# PIC18-USB_ICSP-Board.net
KiCad netlist of a schematic drawn in EAGLE
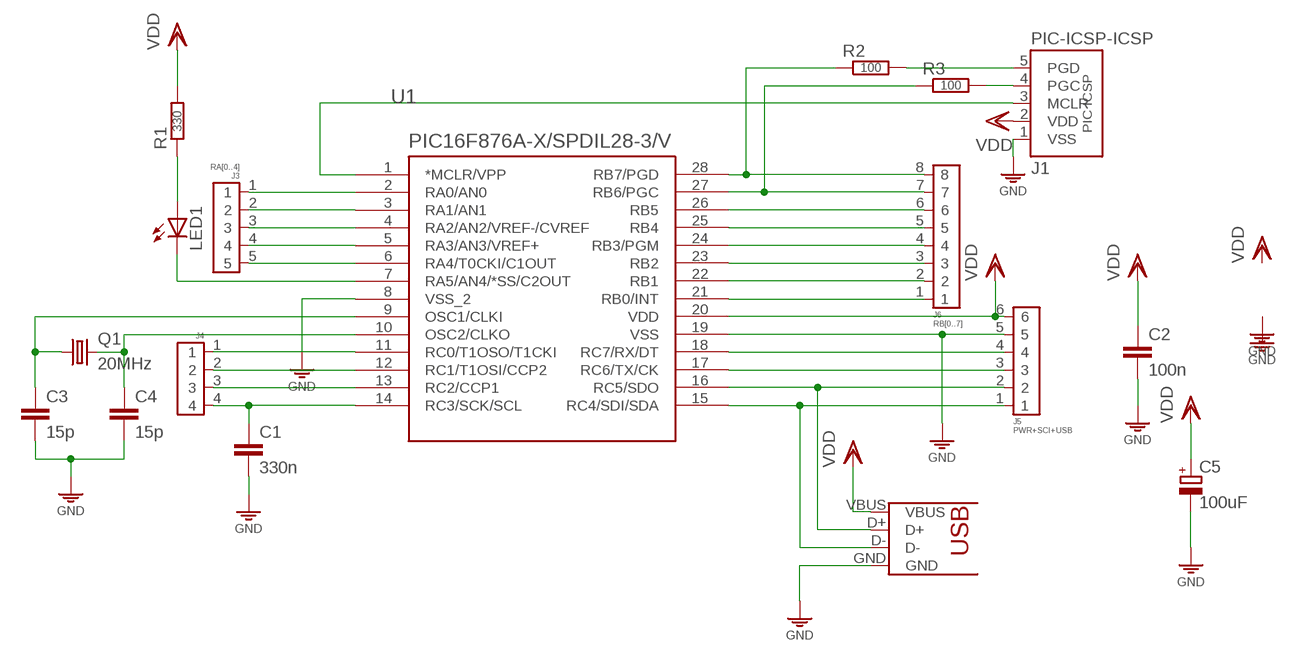
[diagram p0: schematic, sheet 1]

(export (version "E")
  (design (tool "Eeschema 10.0.6"))
  (components
    (comp (ref "C1")
      (value "330n")
      (footprint "eagle-import:C050-030X075")
      (libsource (lib "eagle-import") (part "C050-030X075"))
    )
    (comp (ref "C2")
      (value "100n")
      (footprint "eagle-import:C025-015X024")
      (libsource (lib "eagle-import") (part "C025-015X024"))
    )
    (comp (ref "C3")
      (value "15p")
      (footprint "eagle-import:C025-015X024")
      (libsource (lib "eagle-import") (part "C025-015X024"))
    )
    (comp (ref "C4")
      (value "15p")
      (footprint "eagle-import:C025-015X024")
      (libsource (lib "eagle-import") (part "C025-015X024"))
    )
    (comp (ref "C5")
      (value "100uF")
      (footprint "eagle-import:E2,5-5")
      (libsource (lib "eagle-import") (part "CPOLE2.5-5"))
    )
    (comp (ref "J1")
      (value "PIC-ICSP-ICSP")
      (footprint "eagle-import:PIC-ICSP")
      (libsource (lib "eagle-import") (part "PIC-ICSP-ICSP"))
    )
    (comp (ref "J2")
      (value "USB-PRINT")
      (footprint "eagle-import:USB-B-PRINT")
      (libsource (lib "eagle-import") (part "USB-PRINT"))
    )
    (comp (ref "J3")
      (value "RA[0..4]")
      (footprint "eagle-import:CONN-5P-N")
      (libsource (lib "eagle-import") (part "CONN-5P"))
    )
    (comp (ref "J4")
      (value "RC[0..3]")
      (footprint "eagle-import:CONN-4P")
      (libsource (lib "eagle-import") (part "CONN-4P-4P"))
    )
    (comp (ref "J5")
      (value "PWR+SCI+USB")
      (footprint "eagle-import:CONN-6P")
      (libsource (lib "eagle-import") (part "CONN-6P"))
    )
    (comp (ref "J6")
      (value "RB[0..7]")
      (footprint "eagle-import:CONN-8P")
      (libsource (lib "eagle-import") (part "CONN-8P"))
    )
    (comp (ref "LED1")
      (value "LED3MM")
      (footprint "eagle-import:LED3MM")
      (libsource (lib "eagle-import") (part "LED3MM"))
    )
    (comp (ref "Q1")
      (value "20MHz")
      (footprint "eagle-import:HC49")
      (libsource (lib "eagle-import") (part "CRYSTALHC49"))
    )
    (comp (ref "R1")
      (value "330")
      (footprint "eagle-import:0202_10")
      (libsource (lib "eagle-import") (part "R0202/10"))
    )
    (comp (ref "R2")
      (value "100")
      (footprint "eagle-import:0202_7-V")
      (libsource (lib "eagle-import") (part "R0202/7-V"))
    )
    (comp (ref "R3")
      (value "100")
      (footprint "eagle-import:0202_7-V")
      (libsource (lib "eagle-import") (part "R0202/7-V"))
    )
    (comp (ref "U1")
      (value "PIC16F876A-X/SPDIL28-3/V")
      (footprint "eagle-import:DIL28-3_V")
      (libsource (lib "eagle-import") (part "PIC16F876A-X/SPDIL28-3/V"))
    )
  )
  (nets
    (net (code "1") (name "GND") (class "Default")
      (node (ref "C1") (pin "2") (pinfunction "2_2") (pintype "passive"))
      (node (ref "C2") (pin "2") (pinfunction "2_2") (pintype "passive"))
      (node (ref "C3") (pin "2") (pinfunction "2_2") (pintype "passive"))
      (node (ref "C4") (pin "2") (pinfunction "2_2") (pintype "passive"))
      (node (ref "C5") (pin "-") (pinfunction "-_-") (pintype "passive"))
      (node (ref "J1") (pin "1") (pinfunction "VSS_1") (pintype "passive"))
      (node (ref "J2") (pin "GND") (pinfunction "GND_GND") (pintype "bidirectional"))
      (node (ref "J5") (pin "5") (pinfunction "5_5") (pintype "passive"))
      (node (ref "U1") (pin "19") (pinfunction "VSS_19") (pintype "passive"))
      (node (ref "U1") (pin "8") (pinfunction "VSS_2_8") (pintype "passive"))
    )
    (net (code "2") (name "Net-(J1-MCLR)") (class "Default")
      (node (ref "J1") (pin "3") (pinfunction "MCLR_3") (pintype "passive"))
      (node (ref "U1") (pin "1") (pinfunction "*MCLR/VPP_1") (pintype "passive"))
    )
    (net (code "3") (name "Net-(J1-PGC)") (class "Default")
      (node (ref "J1") (pin "4") (pinfunction "PGC_4") (pintype "passive"))
      (node (ref "R3") (pin "2") (pinfunction "2_2") (pintype "passive"))
    )
    (net (code "4") (name "Net-(J1-PGD)") (class "Default")
      (node (ref "J1") (pin "5") (pinfunction "PGD_5") (pintype "passive"))
      (node (ref "R2") (pin "2") (pinfunction "2_2") (pintype "passive"))
    )
    (net (code "5") (name "Net-(LED1-C)") (class "Default")
      (node (ref "LED1") (pin "K") (pinfunction "C_K") (pintype "passive"))
      (node (ref "U1") (pin "7") (pinfunction "RA5/AN4/*SS/C2OUT_7") (pintype "passive"))
    )
    (net (code "6") (name "Net-(LED1-PadA)") (class "Default")
      (node (ref "LED1") (pin "A") (pinfunction "A_A") (pintype "passive"))
      (node (ref "R1") (pin "1") (pinfunction "1_1") (pintype "passive"))
    )
    (net (code "7") (name "Net-(U1-OSC1{slash}CLKI)") (class "Default")
      (node (ref "C3") (pin "1") (pinfunction "1_1") (pintype "passive"))
      (node (ref "Q1") (pin "1") (pinfunction "1_1") (pintype "passive"))
      (node (ref "U1") (pin "9") (pinfunction "OSC1/CLKI_9") (pintype "passive"))
    )
    (net (code "8") (name "Net-(U1-OSC2{slash}CLKO)") (class "Default")
      (node (ref "C4") (pin "1") (pinfunction "1_1") (pintype "passive"))
      (node (ref "Q1") (pin "2") (pinfunction "2_2") (pintype "passive"))
      (node (ref "U1") (pin "10") (pinfunction "OSC2/CLKO_10") (pintype "passive"))
    )
    (net (code "9") (name "Net-(U1-RA0{slash}AN0)") (class "Default")
      (node (ref "J3") (pin "1") (pinfunction "1_1") (pintype "passive"))
      (node (ref "U1") (pin "2") (pinfunction "RA0/AN0_2") (pintype "passive"))
    )
    (net (code "10") (name "Net-(U1-RA1{slash}AN1)") (class "Default")
      (node (ref "J3") (pin "2") (pinfunction "2_2") (pintype "passive"))
      (node (ref "U1") (pin "3") (pinfunction "RA1/AN1_3") (pintype "passive"))
    )
    (net (code "11") (name "Net-(U1-RA2{slash}AN2{slash}VREF-{slash}CVREF)") (class "Default")
      (node (ref "J3") (pin "3") (pinfunction "3_3") (pintype "passive"))
      (node (ref "U1") (pin "4") (pinfunction "RA2/AN2/VREF-/CVREF_4") (pintype "passive"))
    )
    (net (code "12") (name "Net-(U1-RA3{slash}AN3{slash}VREF+)") (class "Default")
      (node (ref "J3") (pin "4") (pinfunction "4_4") (pintype "passive"))
      (node (ref "U1") (pin "5") (pinfunction "RA3/AN3/VREF+_5") (pintype "passive"))
    )
    (net (code "13") (name "Net-(U1-RA4{slash}T0CKI{slash}C1OUT)") (class "Default")
      (node (ref "J3") (pin "5") (pinfunction "5_5") (pintype "passive"))
      (node (ref "U1") (pin "6") (pinfunction "RA4/T0CKI/C1OUT_6") (pintype "passive"))
    )
    (net (code "14") (name "Net-(U1-RB0{slash}INT)") (class "Default")
      (node (ref "J6") (pin "1") (pinfunction "1_1") (pintype "passive"))
      (node (ref "U1") (pin "21") (pinfunction "RB0/INT_21") (pintype "passive"))
    )
    (net (code "15") (name "Net-(U1-RB1)") (class "Default")
      (node (ref "J6") (pin "2") (pinfunction "2_2") (pintype "passive"))
      (node (ref "U1") (pin "22") (pinfunction "RB1_22") (pintype "passive"))
    )
    (net (code "16") (name "Net-(U1-RB2)") (class "Default")
      (node (ref "J6") (pin "3") (pinfunction "3_3") (pintype "passive"))
      (node (ref "U1") (pin "23") (pinfunction "RB2_23") (pintype "passive"))
    )
    (net (code "17") (name "Net-(U1-RB3{slash}PGM)") (class "Default")
      (node (ref "J6") (pin "4") (pinfunction "4_4") (pintype "passive"))
      (node (ref "U1") (pin "24") (pinfunction "RB3/PGM_24") (pintype "passive"))
    )
    (net (code "18") (name "Net-(U1-RB4)") (class "Default")
      (node (ref "J6") (pin "5") (pinfunction "5_5") (pintype "passive"))
      (node (ref "U1") (pin "25") (pinfunction "RB4_25") (pintype "passive"))
    )
    (net (code "19") (name "Net-(U1-RB5)") (class "Default")
      (node (ref "J6") (pin "6") (pinfunction "6_6") (pintype "passive"))
      (node (ref "U1") (pin "26") (pinfunction "RB5_26") (pintype "passive"))
    )
    (net (code "20") (name "Net-(U1-RB6{slash}PGC)") (class "Default")
      (node (ref "J6") (pin "7") (pinfunction "7_7") (pintype "passive"))
      (node (ref "R3") (pin "1") (pinfunction "1_1") (pintype "passive"))
      (node (ref "U1") (pin "27") (pinfunction "RB6/PGC_27") (pintype "passive"))
    )
    (net (code "21") (name "Net-(U1-RB7{slash}PGD)") (class "Default")
      (node (ref "J6") (pin "8") (pinfunction "8_8") (pintype "passive"))
      (node (ref "R2") (pin "1") (pinfunction "1_1") (pintype "passive"))
      (node (ref "U1") (pin "28") (pinfunction "RB7/PGD_28") (pintype "passive"))
    )
    (net (code "22") (name "Net-(U1-RC0{slash}T1OSO{slash}T1CKI)") (class "Default")
      (node (ref "J4") (pin "1") (pinfunction "1_1") (pintype "bidirectional"))
      (node (ref "U1") (pin "11") (pinfunction "RC0/T1OSO/T1CKI_11") (pintype "passive"))
    )
    (net (code "23") (name "Net-(U1-RC1{slash}T1OSI{slash}CCP2)") (class "Default")
      (node (ref "J4") (pin "2") (pinfunction "2_2") (pintype "bidirectional"))
      (node (ref "U1") (pin "12") (pinfunction "RC1/T1OSI/CCP2_12") (pintype "passive"))
    )
    (net (code "24") (name "Net-(U1-RC2{slash}CCP1)") (class "Default")
      (node (ref "J4") (pin "3") (pinfunction "3_3") (pintype "bidirectional"))
      (node (ref "U1") (pin "13") (pinfunction "RC2/CCP1_13") (pintype "passive"))
    )
    (net (code "25") (name "Net-(U1-RC3{slash}SCK{slash}SCL)") (class "Default")
      (node (ref "C1") (pin "1") (pinfunction "1_1") (pintype "passive"))
      (node (ref "J4") (pin "4") (pinfunction "4_4") (pintype "bidirectional"))
      (node (ref "U1") (pin "14") (pinfunction "RC3/SCK/SCL_14") (pintype "passive"))
    )
    (net (code "26") (name "Net-(U1-RC4{slash}SDI{slash}SDA)") (class "Default")
      (node (ref "J2") (pin "D-") (pinfunction "D-_D-") (pintype "bidirectional"))
      (node (ref "J5") (pin "1") (pinfunction "1_1") (pintype "passive"))
      (node (ref "U1") (pin "15") (pinfunction "RC4/SDI/SDA_15") (pintype "passive"))
    )
    (net (code "27") (name "Net-(U1-RC5{slash}SDO)") (class "Default")
      (node (ref "J2") (pin "D+") (pinfunction "D+_D+") (pintype "bidirectional"))
      (node (ref "J5") (pin "2") (pinfunction "2_2") (pintype "passive"))
      (node (ref "U1") (pin "16") (pinfunction "RC5/SDO_16") (pintype "passive"))
    )
    (net (code "28") (name "Net-(U1-RC6{slash}TX{slash}CK)") (class "Default")
      (node (ref "J5") (pin "3") (pinfunction "3_3") (pintype "passive"))
      (node (ref "U1") (pin "17") (pinfunction "RC6/TX/CK_17") (pintype "passive"))
    )
    (net (code "29") (name "Net-(U1-RC7{slash}RX{slash}DT)") (class "Default")
      (node (ref "J5") (pin "4") (pinfunction "4_4") (pintype "passive"))
      (node (ref "U1") (pin "18") (pinfunction "RC7/RX/DT_18") (pintype "passive"))
    )
    (net (code "30") (name "VDD") (class "Default")
      (node (ref "C2") (pin "1") (pinfunction "1_1") (pintype "passive"))
      (node (ref "C5") (pin "+") (pinfunction "+_+") (pintype "passive"))
      (node (ref "J1") (pin "2") (pinfunction "VDD_2") (pintype "passive"))
      (node (ref "J2") (pin "VBUS") (pinfunction "VBUS_VBUS") (pintype "bidirectional"))
      (node (ref "J5") (pin "6") (pinfunction "6_6") (pintype "passive"))
      (node (ref "R1") (pin "2") (pinfunction "2_2") (pintype "passive"))
      (node (ref "U1") (pin "20") (pinfunction "VDD_20") (pintype "passive"))
    )
  )
)
